# cart_schem.net
KiCad netlist of a schematic drawn in EAGLE
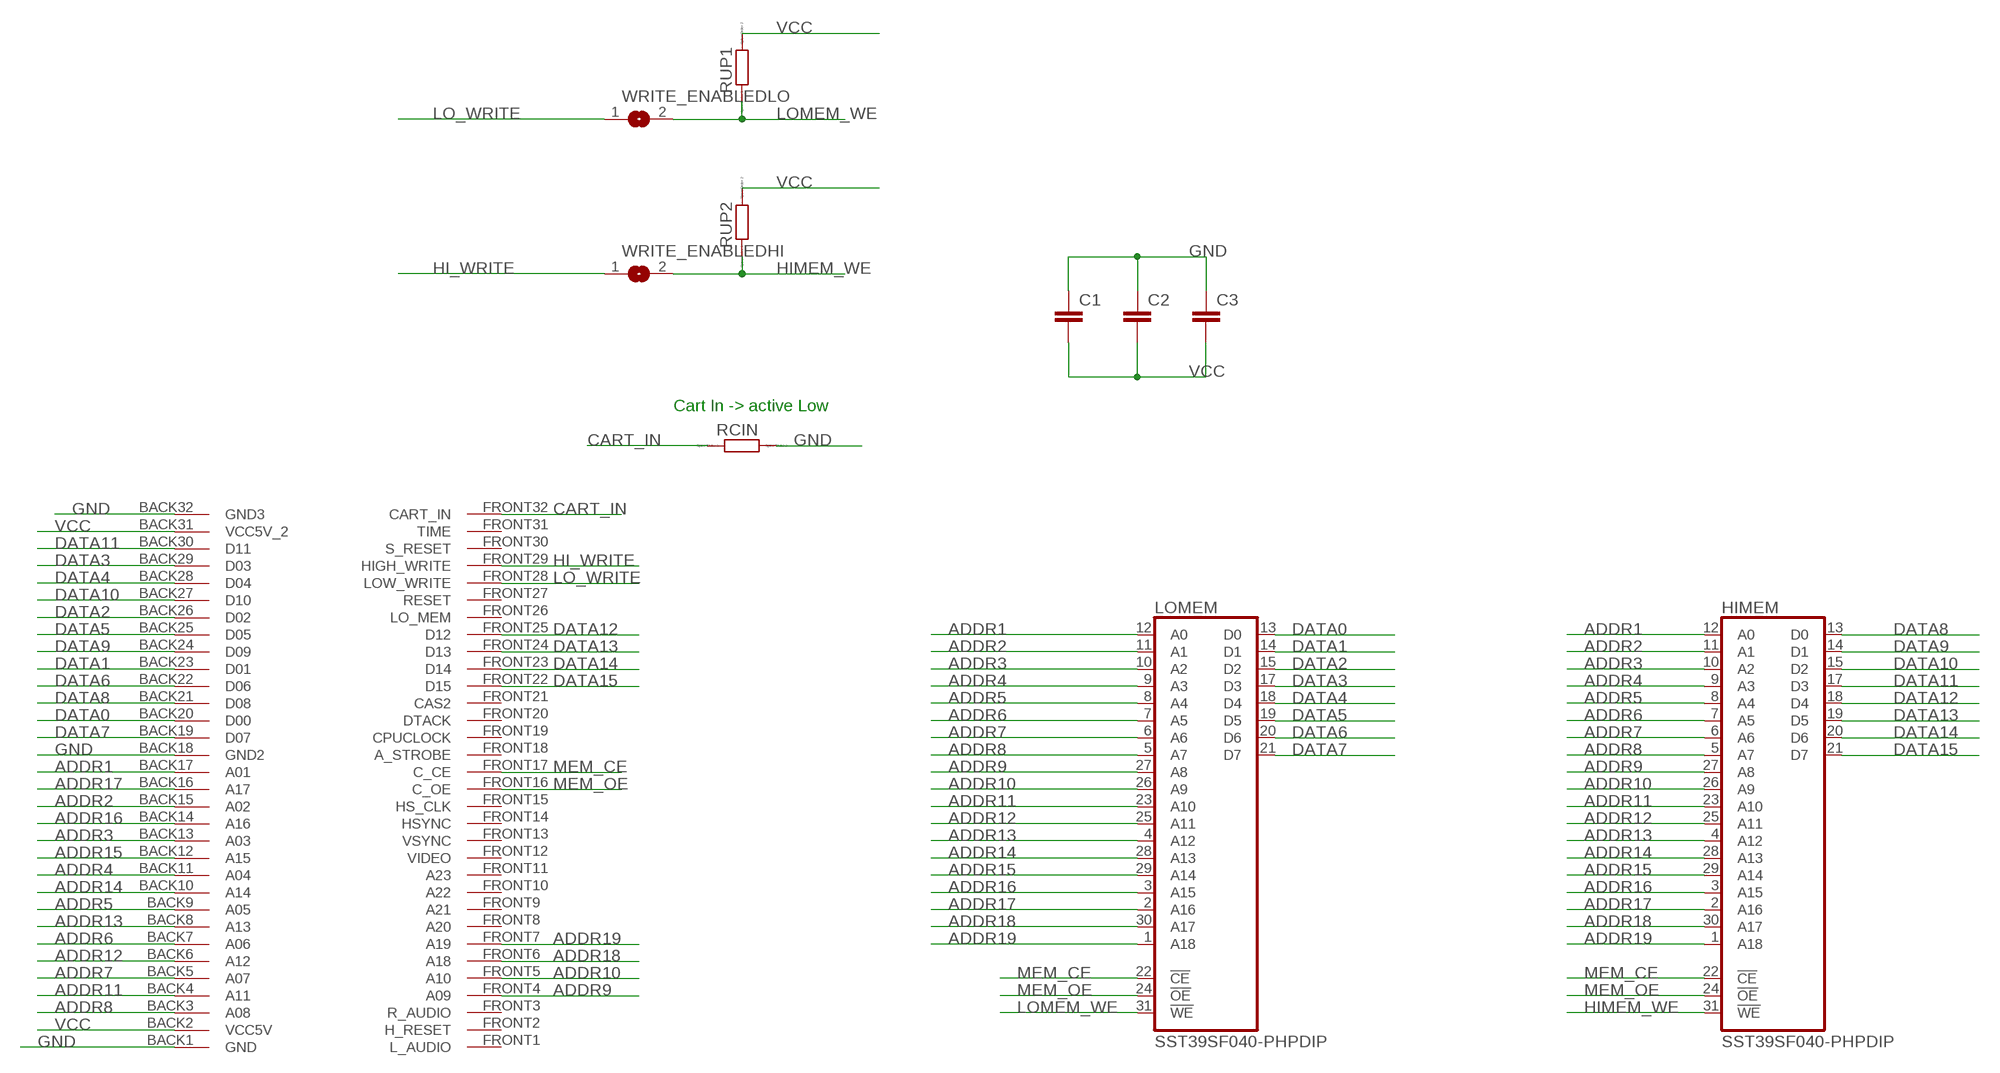
[diagram p0: schematic, sheet 1]

(export (version "E")
  (design (tool "Eeschema 10.0.6"))
  (components
    (comp (ref "C1")
      (value "C-EU025-024X044")
      (footprint "eagle-import:C025-024X044")
      (libsource (lib "eagle-import") (part "C-EU025-024X044"))
    )
    (comp (ref "C2")
      (value "C-EU025-024X044")
      (footprint "eagle-import:C025-024X044")
      (libsource (lib "eagle-import") (part "C-EU025-024X044"))
    )
    (comp (ref "C3")
      (value "C-EU025-024X044")
      (footprint "eagle-import:C025-024X044")
      (libsource (lib "eagle-import") (part "C-EU025-024X044"))
    )
    (comp (ref "HIMEM")
      (value "SST39SF040-PHPDIP")
      (footprint "eagle-import:DIL32")
      (libsource (lib "eagle-import") (part "SST39SF040-PHPDIP"))
    )
    (comp (ref "LOMEM")
      (value "SST39SF040-PHPDIP")
      (footprint "eagle-import:DIL32")
      (libsource (lib "eagle-import") (part "SST39SF040-PHPDIP"))
    )
    (comp (ref "MD1")
      (value "MEGADRIVE-CART")
      (footprint "eagle-import:MEGADRIVE-SLOT-PACKAGE")
      (libsource (lib "eagle-import") (part "MEGADRIVE-CART"))
    )
    (comp (ref "RCIN")
      (value "R0207/10")
      (footprint "eagle-import:0207_10")
      (libsource (lib "eagle-import") (part "R0207/10"))
    )
    (comp (ref "RUP1")
      (value "R0207/10")
      (footprint "eagle-import:0207_10")
      (libsource (lib "eagle-import") (part "R0207/10"))
    )
    (comp (ref "RUP2")
      (value "R0207/10")
      (footprint "eagle-import:0207_10")
      (libsource (lib "eagle-import") (part "R0207/10"))
    )
    (comp (ref "WRITE_ENABLEDHI")
      (value "SJ")
      (footprint "eagle-import:SJ")
      (libsource (lib "eagle-import") (part "SJ"))
    )
    (comp (ref "WRITE_ENABLEDLO")
      (value "SJ")
      (footprint "eagle-import:SJ")
      (libsource (lib "eagle-import") (part "SJ"))
    )
  )
  (nets
    (net (code "1") (name "/ADDR1") (class "Default")
      (node (ref "HIMEM") (pin "12") (pinfunction "A0_12") (pintype "input"))
      (node (ref "LOMEM") (pin "12") (pinfunction "A0_12") (pintype "input"))
      (node (ref "MD1") (pin "BACK17") (pinfunction "A01_BACK17") (pintype "bidirectional"))
    )
    (net (code "2") (name "/ADDR2") (class "Default")
      (node (ref "HIMEM") (pin "11") (pinfunction "A1_11") (pintype "input"))
      (node (ref "LOMEM") (pin "11") (pinfunction "A1_11") (pintype "input"))
      (node (ref "MD1") (pin "BACK15") (pinfunction "A02_BACK15") (pintype "bidirectional"))
    )
    (net (code "3") (name "/ADDR3") (class "Default")
      (node (ref "HIMEM") (pin "10") (pinfunction "A2_10") (pintype "input"))
      (node (ref "LOMEM") (pin "10") (pinfunction "A2_10") (pintype "input"))
      (node (ref "MD1") (pin "BACK13") (pinfunction "A03_BACK13") (pintype "bidirectional"))
    )
    (net (code "4") (name "/ADDR4") (class "Default")
      (node (ref "HIMEM") (pin "9") (pinfunction "A3_9") (pintype "input"))
      (node (ref "LOMEM") (pin "9") (pinfunction "A3_9") (pintype "input"))
      (node (ref "MD1") (pin "BACK11") (pinfunction "A04_BACK11") (pintype "bidirectional"))
    )
    (net (code "5") (name "/ADDR5") (class "Default")
      (node (ref "HIMEM") (pin "8") (pinfunction "A4_8") (pintype "input"))
      (node (ref "LOMEM") (pin "8") (pinfunction "A4_8") (pintype "input"))
      (node (ref "MD1") (pin "BACK9") (pinfunction "A05_BACK9") (pintype "bidirectional"))
    )
    (net (code "6") (name "/ADDR6") (class "Default")
      (node (ref "HIMEM") (pin "7") (pinfunction "A5_7") (pintype "input"))
      (node (ref "LOMEM") (pin "7") (pinfunction "A5_7") (pintype "input"))
      (node (ref "MD1") (pin "BACK7") (pinfunction "A06_BACK7") (pintype "bidirectional"))
    )
    (net (code "7") (name "/ADDR7") (class "Default")
      (node (ref "HIMEM") (pin "6") (pinfunction "A6_6") (pintype "input"))
      (node (ref "LOMEM") (pin "6") (pinfunction "A6_6") (pintype "input"))
      (node (ref "MD1") (pin "BACK5") (pinfunction "A07_BACK5") (pintype "bidirectional"))
    )
    (net (code "8") (name "/ADDR8") (class "Default")
      (node (ref "HIMEM") (pin "5") (pinfunction "A7_5") (pintype "input"))
      (node (ref "LOMEM") (pin "5") (pinfunction "A7_5") (pintype "input"))
      (node (ref "MD1") (pin "BACK3") (pinfunction "A08_BACK3") (pintype "bidirectional"))
    )
    (net (code "9") (name "/ADDR9") (class "Default")
      (node (ref "HIMEM") (pin "27") (pinfunction "A8_27") (pintype "input"))
      (node (ref "LOMEM") (pin "27") (pinfunction "A8_27") (pintype "input"))
      (node (ref "MD1") (pin "FRONT4") (pinfunction "A09_FRONT4") (pintype "bidirectional"))
    )
    (net (code "10") (name "/ADDR10") (class "Default")
      (node (ref "HIMEM") (pin "26") (pinfunction "A9_26") (pintype "input"))
      (node (ref "LOMEM") (pin "26") (pinfunction "A9_26") (pintype "input"))
      (node (ref "MD1") (pin "FRONT5") (pinfunction "A10_FRONT5") (pintype "bidirectional"))
    )
    (net (code "11") (name "/ADDR11") (class "Default")
      (node (ref "HIMEM") (pin "23") (pinfunction "A10_23") (pintype "input"))
      (node (ref "LOMEM") (pin "23") (pinfunction "A10_23") (pintype "input"))
      (node (ref "MD1") (pin "BACK4") (pinfunction "A11_BACK4") (pintype "bidirectional"))
    )
    (net (code "12") (name "/ADDR12") (class "Default")
      (node (ref "HIMEM") (pin "25") (pinfunction "A11_25") (pintype "input"))
      (node (ref "LOMEM") (pin "25") (pinfunction "A11_25") (pintype "input"))
      (node (ref "MD1") (pin "BACK6") (pinfunction "A12_BACK6") (pintype "bidirectional"))
    )
    (net (code "13") (name "/ADDR13") (class "Default")
      (node (ref "HIMEM") (pin "4") (pinfunction "A12_4") (pintype "input"))
      (node (ref "LOMEM") (pin "4") (pinfunction "A12_4") (pintype "input"))
      (node (ref "MD1") (pin "BACK8") (pinfunction "A13_BACK8") (pintype "bidirectional"))
    )
    (net (code "14") (name "/ADDR14") (class "Default")
      (node (ref "HIMEM") (pin "28") (pinfunction "A13_28") (pintype "input"))
      (node (ref "LOMEM") (pin "28") (pinfunction "A13_28") (pintype "input"))
      (node (ref "MD1") (pin "BACK10") (pinfunction "A14_BACK10") (pintype "bidirectional"))
    )
    (net (code "15") (name "/ADDR15") (class "Default")
      (node (ref "HIMEM") (pin "29") (pinfunction "A14_29") (pintype "input"))
      (node (ref "LOMEM") (pin "29") (pinfunction "A14_29") (pintype "input"))
      (node (ref "MD1") (pin "BACK12") (pinfunction "A15_BACK12") (pintype "bidirectional"))
    )
    (net (code "16") (name "/ADDR16") (class "Default")
      (node (ref "HIMEM") (pin "3") (pinfunction "A15_3") (pintype "input"))
      (node (ref "LOMEM") (pin "3") (pinfunction "A15_3") (pintype "input"))
      (node (ref "MD1") (pin "BACK14") (pinfunction "A16_BACK14") (pintype "bidirectional"))
    )
    (net (code "17") (name "/ADDR17") (class "Default")
      (node (ref "HIMEM") (pin "2") (pinfunction "A16_2") (pintype "input"))
      (node (ref "LOMEM") (pin "2") (pinfunction "A16_2") (pintype "input"))
      (node (ref "MD1") (pin "BACK16") (pinfunction "A17_BACK16") (pintype "bidirectional"))
    )
    (net (code "18") (name "/ADDR18") (class "Default")
      (node (ref "HIMEM") (pin "30") (pinfunction "A17_30") (pintype "input"))
      (node (ref "LOMEM") (pin "30") (pinfunction "A17_30") (pintype "input"))
      (node (ref "MD1") (pin "FRONT6") (pinfunction "A18_FRONT6") (pintype "bidirectional"))
    )
    (net (code "19") (name "/ADDR19") (class "Default")
      (node (ref "HIMEM") (pin "1") (pinfunction "A18_1") (pintype "input"))
      (node (ref "LOMEM") (pin "1") (pinfunction "A18_1") (pintype "input"))
      (node (ref "MD1") (pin "FRONT7") (pinfunction "A19_FRONT7") (pintype "bidirectional"))
    )
    (net (code "20") (name "/CART_IN") (class "Default")
      (node (ref "MD1") (pin "FRONT32") (pinfunction "CART_IN_FRONT32") (pintype "bidirectional"))
      (node (ref "RCIN") (pin "1") (pinfunction "1_1") (pintype "passive"))
    )
    (net (code "21") (name "/DATA0") (class "Default")
      (node (ref "LOMEM") (pin "13") (pinfunction "D0_13") (pintype "bidirectional"))
      (node (ref "MD1") (pin "BACK20") (pinfunction "D00_BACK20") (pintype "bidirectional"))
    )
    (net (code "22") (name "/DATA1") (class "Default")
      (node (ref "LOMEM") (pin "14") (pinfunction "D1_14") (pintype "bidirectional"))
      (node (ref "MD1") (pin "BACK23") (pinfunction "D01_BACK23") (pintype "bidirectional"))
    )
    (net (code "23") (name "/DATA2") (class "Default")
      (node (ref "LOMEM") (pin "15") (pinfunction "D2_15") (pintype "bidirectional"))
      (node (ref "MD1") (pin "BACK26") (pinfunction "D02_BACK26") (pintype "bidirectional"))
    )
    (net (code "24") (name "/DATA3") (class "Default")
      (node (ref "LOMEM") (pin "17") (pinfunction "D3_17") (pintype "bidirectional"))
      (node (ref "MD1") (pin "BACK29") (pinfunction "D03_BACK29") (pintype "bidirectional"))
    )
    (net (code "25") (name "/DATA4") (class "Default")
      (node (ref "LOMEM") (pin "18") (pinfunction "D4_18") (pintype "bidirectional"))
      (node (ref "MD1") (pin "BACK28") (pinfunction "D04_BACK28") (pintype "bidirectional"))
    )
    (net (code "26") (name "/DATA5") (class "Default")
      (node (ref "LOMEM") (pin "19") (pinfunction "D5_19") (pintype "bidirectional"))
      (node (ref "MD1") (pin "BACK25") (pinfunction "D05_BACK25") (pintype "bidirectional"))
    )
    (net (code "27") (name "/DATA6") (class "Default")
      (node (ref "LOMEM") (pin "20") (pinfunction "D6_20") (pintype "bidirectional"))
      (node (ref "MD1") (pin "BACK22") (pinfunction "D06_BACK22") (pintype "bidirectional"))
    )
    (net (code "28") (name "/DATA7") (class "Default")
      (node (ref "LOMEM") (pin "21") (pinfunction "D7_21") (pintype "bidirectional"))
      (node (ref "MD1") (pin "BACK19") (pinfunction "D07_BACK19") (pintype "bidirectional"))
    )
    (net (code "29") (name "/DATA8") (class "Default")
      (node (ref "HIMEM") (pin "13") (pinfunction "D0_13") (pintype "bidirectional"))
      (node (ref "MD1") (pin "BACK21") (pinfunction "D08_BACK21") (pintype "bidirectional"))
    )
    (net (code "30") (name "/DATA9") (class "Default")
      (node (ref "HIMEM") (pin "14") (pinfunction "D1_14") (pintype "bidirectional"))
      (node (ref "MD1") (pin "BACK24") (pinfunction "D09_BACK24") (pintype "bidirectional"))
    )
    (net (code "31") (name "/DATA10") (class "Default")
      (node (ref "HIMEM") (pin "15") (pinfunction "D2_15") (pintype "bidirectional"))
      (node (ref "MD1") (pin "BACK27") (pinfunction "D10_BACK27") (pintype "bidirectional"))
    )
    (net (code "32") (name "/DATA11") (class "Default")
      (node (ref "HIMEM") (pin "17") (pinfunction "D3_17") (pintype "bidirectional"))
      (node (ref "MD1") (pin "BACK30") (pinfunction "D11_BACK30") (pintype "bidirectional"))
    )
    (net (code "33") (name "/DATA12") (class "Default")
      (node (ref "HIMEM") (pin "18") (pinfunction "D4_18") (pintype "bidirectional"))
      (node (ref "MD1") (pin "FRONT25") (pinfunction "D12_FRONT25") (pintype "bidirectional"))
    )
    (net (code "34") (name "/DATA13") (class "Default")
      (node (ref "HIMEM") (pin "19") (pinfunction "D5_19") (pintype "bidirectional"))
      (node (ref "MD1") (pin "FRONT24") (pinfunction "D13_FRONT24") (pintype "bidirectional"))
    )
    (net (code "35") (name "/DATA14") (class "Default")
      (node (ref "HIMEM") (pin "20") (pinfunction "D6_20") (pintype "bidirectional"))
      (node (ref "MD1") (pin "FRONT23") (pinfunction "D14_FRONT23") (pintype "bidirectional"))
    )
    (net (code "36") (name "/DATA15") (class "Default")
      (node (ref "HIMEM") (pin "21") (pinfunction "D7_21") (pintype "bidirectional"))
      (node (ref "MD1") (pin "FRONT22") (pinfunction "D15_FRONT22") (pintype "bidirectional"))
    )
    (net (code "37") (name "/GND") (class "Default")
      (node (ref "C1") (pin "1") (pinfunction "1_1") (pintype "passive"))
      (node (ref "C2") (pin "1") (pinfunction "1_1") (pintype "passive"))
      (node (ref "C3") (pin "1") (pinfunction "1_1") (pintype "passive"))
      (node (ref "MD1") (pin "BACK1") (pinfunction "GND_BACK1") (pintype "bidirectional"))
      (node (ref "MD1") (pin "BACK18") (pinfunction "GND2_BACK18") (pintype "bidirectional"))
      (node (ref "MD1") (pin "BACK32") (pinfunction "GND3_BACK32") (pintype "bidirectional"))
      (node (ref "RCIN") (pin "2") (pinfunction "2_2") (pintype "passive"))
    )
    (net (code "38") (name "/HIMEM_WE") (class "Default")
      (node (ref "HIMEM") (pin "31") (pinfunction "~{WE}_31") (pintype "input"))
      (node (ref "RUP2") (pin "1") (pinfunction "1_1") (pintype "passive"))
      (node (ref "WRITE_ENABLEDHI") (pin "2") (pinfunction "2_2") (pintype "passive"))
    )
    (net (code "39") (name "/HI_WRITE") (class "Default")
      (node (ref "MD1") (pin "FRONT29") (pinfunction "HIGH_WRITE_FRONT29") (pintype "bidirectional"))
      (node (ref "WRITE_ENABLEDHI") (pin "1") (pinfunction "1_1") (pintype "passive"))
    )
    (net (code "40") (name "/LOMEM_WE") (class "Default")
      (node (ref "LOMEM") (pin "31") (pinfunction "~{WE}_31") (pintype "input"))
      (node (ref "RUP1") (pin "1") (pinfunction "1_1") (pintype "passive"))
      (node (ref "WRITE_ENABLEDLO") (pin "2") (pinfunction "2_2") (pintype "passive"))
    )
    (net (code "41") (name "/LO_WRITE") (class "Default")
      (node (ref "MD1") (pin "FRONT28") (pinfunction "LOW_WRITE_FRONT28") (pintype "bidirectional"))
      (node (ref "WRITE_ENABLEDLO") (pin "1") (pinfunction "1_1") (pintype "passive"))
    )
    (net (code "42") (name "/MEM_CE") (class "Default")
      (node (ref "HIMEM") (pin "22") (pinfunction "~{CE}_22") (pintype "input"))
      (node (ref "LOMEM") (pin "22") (pinfunction "~{CE}_22") (pintype "input"))
      (node (ref "MD1") (pin "FRONT17") (pinfunction "C_CE_FRONT17") (pintype "bidirectional"))
    )
    (net (code "43") (name "/MEM_OE") (class "Default")
      (node (ref "HIMEM") (pin "24") (pinfunction "~{OE}_24") (pintype "input"))
      (node (ref "LOMEM") (pin "24") (pinfunction "~{OE}_24") (pintype "input"))
      (node (ref "MD1") (pin "FRONT16") (pinfunction "C_OE_FRONT16") (pintype "bidirectional"))
    )
    (net (code "44") (name "/VCC") (class "Default")
      (node (ref "C1") (pin "2") (pinfunction "2_2") (pintype "passive"))
      (node (ref "C2") (pin "2") (pinfunction "2_2") (pintype "passive"))
      (node (ref "C3") (pin "2") (pinfunction "2_2") (pintype "passive"))
      (node (ref "MD1") (pin "BACK2") (pinfunction "VCC5V_BACK2") (pintype "bidirectional"))
      (node (ref "MD1") (pin "BACK31") (pinfunction "VCC5V_2_BACK31") (pintype "bidirectional"))
      (node (ref "RUP1") (pin "2") (pinfunction "2_2") (pintype "passive"))
      (node (ref "RUP2") (pin "2") (pinfunction "2_2") (pintype "passive"))
    )
    (net (code "45") (name "unconnected-(MD1-A20-PadFRONT8)") (class "Default")
      (node (ref "MD1") (pin "FRONT8") (pinfunction "A20_FRONT8") (pintype "bidirectional"))
    )
    (net (code "46") (name "unconnected-(MD1-A21-PadFRONT9)") (class "Default")
      (node (ref "MD1") (pin "FRONT9") (pinfunction "A21_FRONT9") (pintype "bidirectional"))
    )
    (net (code "47") (name "unconnected-(MD1-A22-PadFRONT10)") (class "Default")
      (node (ref "MD1") (pin "FRONT10") (pinfunction "A22_FRONT10") (pintype "bidirectional"))
    )
    (net (code "48") (name "unconnected-(MD1-A23-PadFRONT11)") (class "Default")
      (node (ref "MD1") (pin "FRONT11") (pinfunction "A23_FRONT11") (pintype "bidirectional"))
    )
    (net (code "49") (name "unconnected-(MD1-A_STROBE-PadFRONT18)") (class "Default")
      (node (ref "MD1") (pin "FRONT18") (pinfunction "A_STROBE_FRONT18") (pintype "bidirectional"))
    )
    (net (code "50") (name "unconnected-(MD1-CAS2-PadFRONT21)") (class "Default")
      (node (ref "MD1") (pin "FRONT21") (pinfunction "CAS2_FRONT21") (pintype "bidirectional"))
    )
    (net (code "51") (name "unconnected-(MD1-CPUCLOCK-PadFRONT19)") (class "Default")
      (node (ref "MD1") (pin "FRONT19") (pinfunction "CPUCLOCK_FRONT19") (pintype "bidirectional"))
    )
    (net (code "52") (name "unconnected-(MD1-DTACK-PadFRONT20)") (class "Default")
      (node (ref "MD1") (pin "FRONT20") (pinfunction "DTACK_FRONT20") (pintype "bidirectional"))
    )
    (net (code "53") (name "unconnected-(MD1-HSYNC-PadFRONT14)") (class "Default")
      (node (ref "MD1") (pin "FRONT14") (pinfunction "HSYNC_FRONT14") (pintype "bidirectional"))
    )
    (net (code "54") (name "unconnected-(MD1-HS_CLK-PadFRONT15)") (class "Default")
      (node (ref "MD1") (pin "FRONT15") (pinfunction "HS_CLK_FRONT15") (pintype "bidirectional"))
    )
    (net (code "55") (name "unconnected-(MD1-H_RESET-PadFRONT2)") (class "Default")
      (node (ref "MD1") (pin "FRONT2") (pinfunction "H_RESET_FRONT2") (pintype "bidirectional"))
    )
    (net (code "56") (name "unconnected-(MD1-LO_MEM-PadFRONT26)") (class "Default")
      (node (ref "MD1") (pin "FRONT26") (pinfunction "LO_MEM_FRONT26") (pintype "bidirectional"))
    )
    (net (code "57") (name "unconnected-(MD1-L_AUDIO-PadFRONT1)") (class "Default")
      (node (ref "MD1") (pin "FRONT1") (pinfunction "L_AUDIO_FRONT1") (pintype "bidirectional"))
    )
    (net (code "58") (name "unconnected-(MD1-RESET-PadFRONT27)") (class "Default")
      (node (ref "MD1") (pin "FRONT27") (pinfunction "RESET_FRONT27") (pintype "bidirectional"))
    )
    (net (code "59") (name "unconnected-(MD1-R_AUDIO-PadFRONT3)") (class "Default")
      (node (ref "MD1") (pin "FRONT3") (pinfunction "R_AUDIO_FRONT3") (pintype "bidirectional"))
    )
    (net (code "60") (name "unconnected-(MD1-S_RESET-PadFRONT30)") (class "Default")
      (node (ref "MD1") (pin "FRONT30") (pinfunction "S_RESET_FRONT30") (pintype "bidirectional"))
    )
    (net (code "61") (name "unconnected-(MD1-TIME-PadFRONT31)") (class "Default")
      (node (ref "MD1") (pin "FRONT31") (pinfunction "TIME_FRONT31") (pintype "bidirectional"))
    )
    (net (code "62") (name "unconnected-(MD1-VIDEO-PadFRONT12)") (class "Default")
      (node (ref "MD1") (pin "FRONT12") (pinfunction "VIDEO_FRONT12") (pintype "bidirectional"))
    )
    (net (code "63") (name "unconnected-(MD1-VSYNC-PadFRONT13)") (class "Default")
      (node (ref "MD1") (pin "FRONT13") (pinfunction "VSYNC_FRONT13") (pintype "bidirectional"))
    )
  )
)
